# roboteq.net
KiCad netlist of a schematic drawn in EAGLE
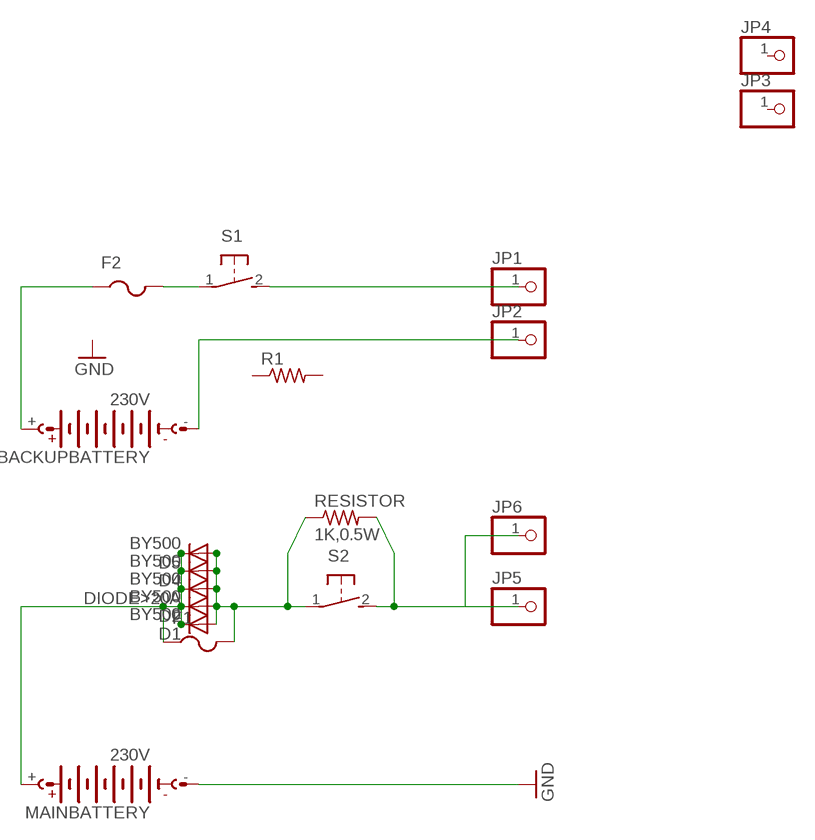
[diagram p0: schematic, sheet 1]

(export (version "E")
  (design (tool "Eeschema 10.0.6"))
  (components
    (comp (ref "BACKUPBATTERY")
      (value "230V")
      (footprint "eagle-import:AB9V")
      (libsource (lib "eagle-import") (part "AB9V"))
    )
    (comp (ref "D1")
      (value "BY500")
      (footprint "eagle-import:DO201-15")
      (libsource (lib "eagle-import") (part "BY500"))
    )
    (comp (ref "D2")
      (value "BY500")
      (footprint "eagle-import:DO201-15")
      (libsource (lib "eagle-import") (part "BY500"))
    )
    (comp (ref "D4")
      (value "BY500")
      (footprint "eagle-import:DO201-15")
      (libsource (lib "eagle-import") (part "BY500"))
    )
    (comp (ref "D5")
      (value "BY500")
      (footprint "eagle-import:DO201-15")
      (libsource (lib "eagle-import") (part "BY500"))
    )
    (comp (ref "DIODE>20A")
      (value "BY500")
      (footprint "eagle-import:DO201-15")
      (libsource (lib "eagle-import") (part "BY500"))
    )
    (comp (ref "F1")
      (value "PTCFUSE-1206")
      (footprint "eagle-import:R1206")
      (libsource (lib "eagle-import") (part "PTCFUSE-1206"))
    )
    (comp (ref "F2")
      (value "PTCFUSE-1206")
      (footprint "eagle-import:R1206")
      (libsource (lib "eagle-import") (part "PTCFUSE-1206"))
    )
    (comp (ref "JP1")
      (value "PINHD-1X1")
      (footprint "eagle-import:1X01")
      (libsource (lib "eagle-import") (part "PINHD-1X1"))
    )
    (comp (ref "JP2")
      (value "PINHD-1X1")
      (footprint "eagle-import:1X01")
      (libsource (lib "eagle-import") (part "PINHD-1X1"))
    )
    (comp (ref "JP3")
      (value "PINHD-1X1")
      (footprint "eagle-import:1X01")
      (libsource (lib "eagle-import") (part "PINHD-1X1"))
    )
    (comp (ref "JP4")
      (value "PINHD-1X1")
      (footprint "eagle-import:1X01")
      (libsource (lib "eagle-import") (part "PINHD-1X1"))
    )
    (comp (ref "JP5")
      (value "PINHD-1X1")
      (footprint "eagle-import:1X01")
      (libsource (lib "eagle-import") (part "PINHD-1X1"))
    )
    (comp (ref "JP6")
      (value "PINHD-1X1")
      (footprint "eagle-import:1X01")
      (libsource (lib "eagle-import") (part "PINHD-1X1"))
    )
    (comp (ref "MAINBATTERY")
      (value "230V")
      (footprint "eagle-import:AB9V")
      (libsource (lib "eagle-import") (part "AB9V"))
    )
    (comp (ref "R1")
      (value "R-US_0204/5")
      (footprint "eagle-import:0204_5")
      (libsource (lib "eagle-import") (part "R-US_0204/5"))
    )
    (comp (ref "RESISTOR")
      (value "1K,0.5W")
      (footprint "eagle-import:0204_5")
      (libsource (lib "eagle-import") (part "R-US_0204/5"))
    )
    (comp (ref "S1")
      (value "31-XX")
      (footprint "eagle-import:B3F-31XX")
      (libsource (lib "eagle-import") (part "31-XX"))
    )
    (comp (ref "S2")
      (value "31-XX")
      (footprint "eagle-import:B3F-31XX")
      (libsource (lib "eagle-import") (part "31-XX"))
    )
  )
  (nets
    (net (code "1") (name "GND") (class "Default")
      (node (ref "MAINBATTERY") (pin "-") (pinfunction "-_-") (pintype "passive"))
    )
    (net (code "2") (name "Net-(BACKUPBATTERY-Pad+)") (class "Default")
      (node (ref "BACKUPBATTERY") (pin "+") (pinfunction "+_+") (pintype "passive"))
      (node (ref "F2") (pin "1") (pinfunction "1_1") (pintype "passive"))
    )
    (net (code "3") (name "Net-(BACKUPBATTERY-Pad-)") (class "Default")
      (node (ref "BACKUPBATTERY") (pin "-") (pinfunction "-_-") (pintype "passive"))
      (node (ref "JP2") (pin "1") (pinfunction "1_1") (pintype "passive"))
    )
    (net (code "4") (name "Net-(D1-PadC)") (class "Default")
      (node (ref "D1") (pin "C") (pinfunction "C_C") (pintype "passive"))
      (node (ref "D2") (pin "C") (pinfunction "C_C") (pintype "passive"))
      (node (ref "D4") (pin "C") (pinfunction "C_C") (pintype "passive"))
      (node (ref "D5") (pin "C") (pinfunction "C_C") (pintype "passive"))
      (node (ref "DIODE>20A") (pin "C") (pinfunction "C_C") (pintype "passive"))
      (node (ref "F1") (pin "1") (pinfunction "1_1") (pintype "passive"))
      (node (ref "MAINBATTERY") (pin "+") (pinfunction "+_+") (pintype "passive"))
    )
    (net (code "5") (name "Net-(S1-P)") (class "Default")
      (node (ref "F2") (pin "2") (pinfunction "2_2") (pintype "passive"))
      (node (ref "S1") (pin "1") (pinfunction "P_1") (pintype "passive"))
    )
    (net (code "6") (name "Net-(S1-S)") (class "Default")
      (node (ref "JP1") (pin "1") (pinfunction "1_1") (pintype "passive"))
      (node (ref "S1") (pin "2") (pinfunction "S_2") (pintype "passive"))
    )
    (net (code "7") (name "Net-(S2-P)") (class "Default")
      (node (ref "D1") (pin "A") (pinfunction "A_A") (pintype "passive"))
      (node (ref "D2") (pin "A") (pinfunction "A_A") (pintype "passive"))
      (node (ref "D4") (pin "A") (pinfunction "A_A") (pintype "passive"))
      (node (ref "D5") (pin "A") (pinfunction "A_A") (pintype "passive"))
      (node (ref "DIODE>20A") (pin "A") (pinfunction "A_A") (pintype "passive"))
      (node (ref "F1") (pin "2") (pinfunction "2_2") (pintype "passive"))
      (node (ref "RESISTOR") (pin "1") (pinfunction "1_1") (pintype "passive"))
      (node (ref "S2") (pin "1") (pinfunction "P_1") (pintype "passive"))
    )
    (net (code "8") (name "Net-(S2-S)") (class "Default")
      (node (ref "JP5") (pin "1") (pinfunction "1_1") (pintype "passive"))
      (node (ref "JP6") (pin "1") (pinfunction "1_1") (pintype "passive"))
      (node (ref "RESISTOR") (pin "2") (pinfunction "2_2") (pintype "passive"))
      (node (ref "S2") (pin "2") (pinfunction "S_2") (pintype "passive"))
    )
    (net (code "9") (name "unconnected-(JP3-Pad1)") (class "Default")
      (node (ref "JP3") (pin "1") (pinfunction "1_1") (pintype "passive"))
    )
    (net (code "10") (name "unconnected-(JP4-Pad1)") (class "Default")
      (node (ref "JP4") (pin "1") (pinfunction "1_1") (pintype "passive"))
    )
    (net (code "11") (name "unconnected-(R1-Pad1)") (class "Default")
      (node (ref "R1") (pin "1") (pinfunction "1_1") (pintype "passive"))
    )
    (net (code "12") (name "unconnected-(R1-Pad2)") (class "Default")
      (node (ref "R1") (pin "2") (pinfunction "2_2") (pintype "passive"))
    )
  )
)
